# Thermosistor2.net
KiCad netlist of a schematic drawn in Altium Designer
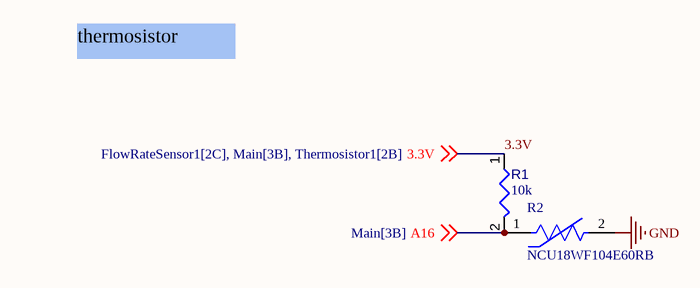
[diagram p0: Thermosistor2.SchDoc]

(export (version "E")
  (design (tool "Eeschema 10.0.6"))
  (components
    (comp (ref "R1")
      (value "10k")
      (footprint "RESC0402(1005)_L")
      (description "Chip Resistor, 10 kOhms, +/-1 %, 63 mW, -55 to 125 degC, 0402")
      (fields (field (name "POWER") "63mW") (field (name "TOLERANCE") "1%"))
      (libsource (lib "Alt_ium Course") (part "RES-2"))
    )
    (comp (ref "R2")
      (value "NCU18WF104E60RB")
      (footprint "FP-NCU18-0_15-IPC_C")
      (description "THERMISTOR NTC")
      (libsource (lib "Altium Content Vault") (part "3b148a6ebabc5fb4d708a66c052d352"))
    )
  )
  (nets
    (net (code "1") (name "3.3V") (class "Default")
      (node (ref "R1") (pin "1") (pinfunction "1_1") (pintype "passive"))
    )
    (net (code "2") (name "A16") (class "Default")
      (node (ref "R1") (pin "2") (pinfunction "2_2") (pintype "passive"))
      (node (ref "R2") (pin "1") (pinfunction "1_1") (pintype "passive"))
    )
    (net (code "3") (name "GND") (class "Default")
      (node (ref "R2") (pin "2") (pinfunction "2_2") (pintype "passive"))
    )
  )
)
